# RVPOVP.net
KiCad netlist of a schematic drawn in Altium Designer
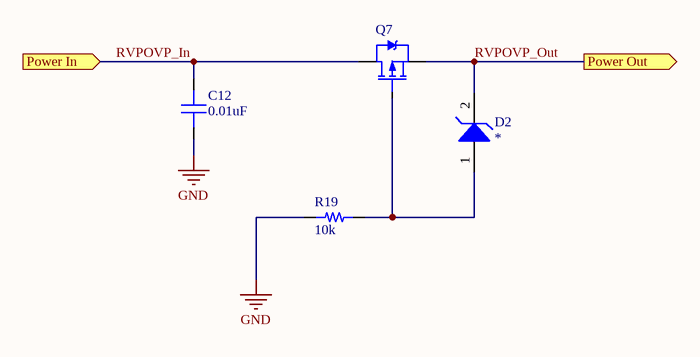
[diagram p0: RVPOVP.SchDoc]

(export (version "E")
  (design (tool "Eeschema 10.0.6"))
  (components
    (comp (ref "C12")
      (value "capacitor")
      (footprint "0603")
      (description "Generic 0603 capacitor")
      (fields (field (name "CAPACITANCE") "0.01uF") (field (name "VOLTAGE") "50"))
      (libsource (lib "altlib") (part "capacitor"))
    )
    (comp (ref "D2")
      (value "*")
      (footprint "SOD123F")
      (description "Zener Diode 14V 500mW ±5% Surface Mount SOD-1")
      (libsource (lib "altlib") (part "Zener"))
    )
    (comp (ref "Q7")
      (value "DMP3010LK3-13")
      (footprint "DMP3010LK3-13")
      (description "P-Channel MOSFET 30V 17A TO252")
      (fields (field (name "CREATEDBY") "Kevin"))
      (libsource (lib "altlib") (part "DMP3010LK3-13"))
    )
    (comp (ref "R19")
      (value "resistor")
      (footprint "0603")
      (fields (field (name "RESISTANCE") "10k"))
      (libsource (lib "altlib") (part "resistor"))
    )
  )
  (nets
    (net (code "1") (name "/RVPOVP_In") (class "Default")
      (node (ref "C12") (pin "2") (pinfunction "2_2") (pintype "passive"))
      (node (ref "Q7") (pin "3") (pinfunction "D_3") (pintype "passive"))
    )
    (net (code "2") (name "/RVPOVP_Out") (class "Default")
      (node (ref "D2") (pin "2") (pinfunction "K_2") (pintype "passive"))
      (node (ref "Q7") (pin "2") (pinfunction "S_2") (pintype "passive"))
    )
    (net (code "3") (name "GND") (class "Default")
      (node (ref "C12") (pin "1") (pinfunction "1_1") (pintype "passive"))
      (node (ref "R19") (pin "1") (pinfunction "1_1") (pintype "passive"))
    )
    (net (code "4") (name "Net-(D2-A)") (class "Default")
      (node (ref "D2") (pin "1") (pinfunction "A_1") (pintype "passive"))
      (node (ref "Q7") (pin "1") (pinfunction "G_1") (pintype "passive"))
      (node (ref "R19") (pin "2") (pinfunction "2_2") (pintype "passive"))
    )
  )
)
